# Kintex7_ssram.net
KiCad netlist of a schematic drawn in EAGLE
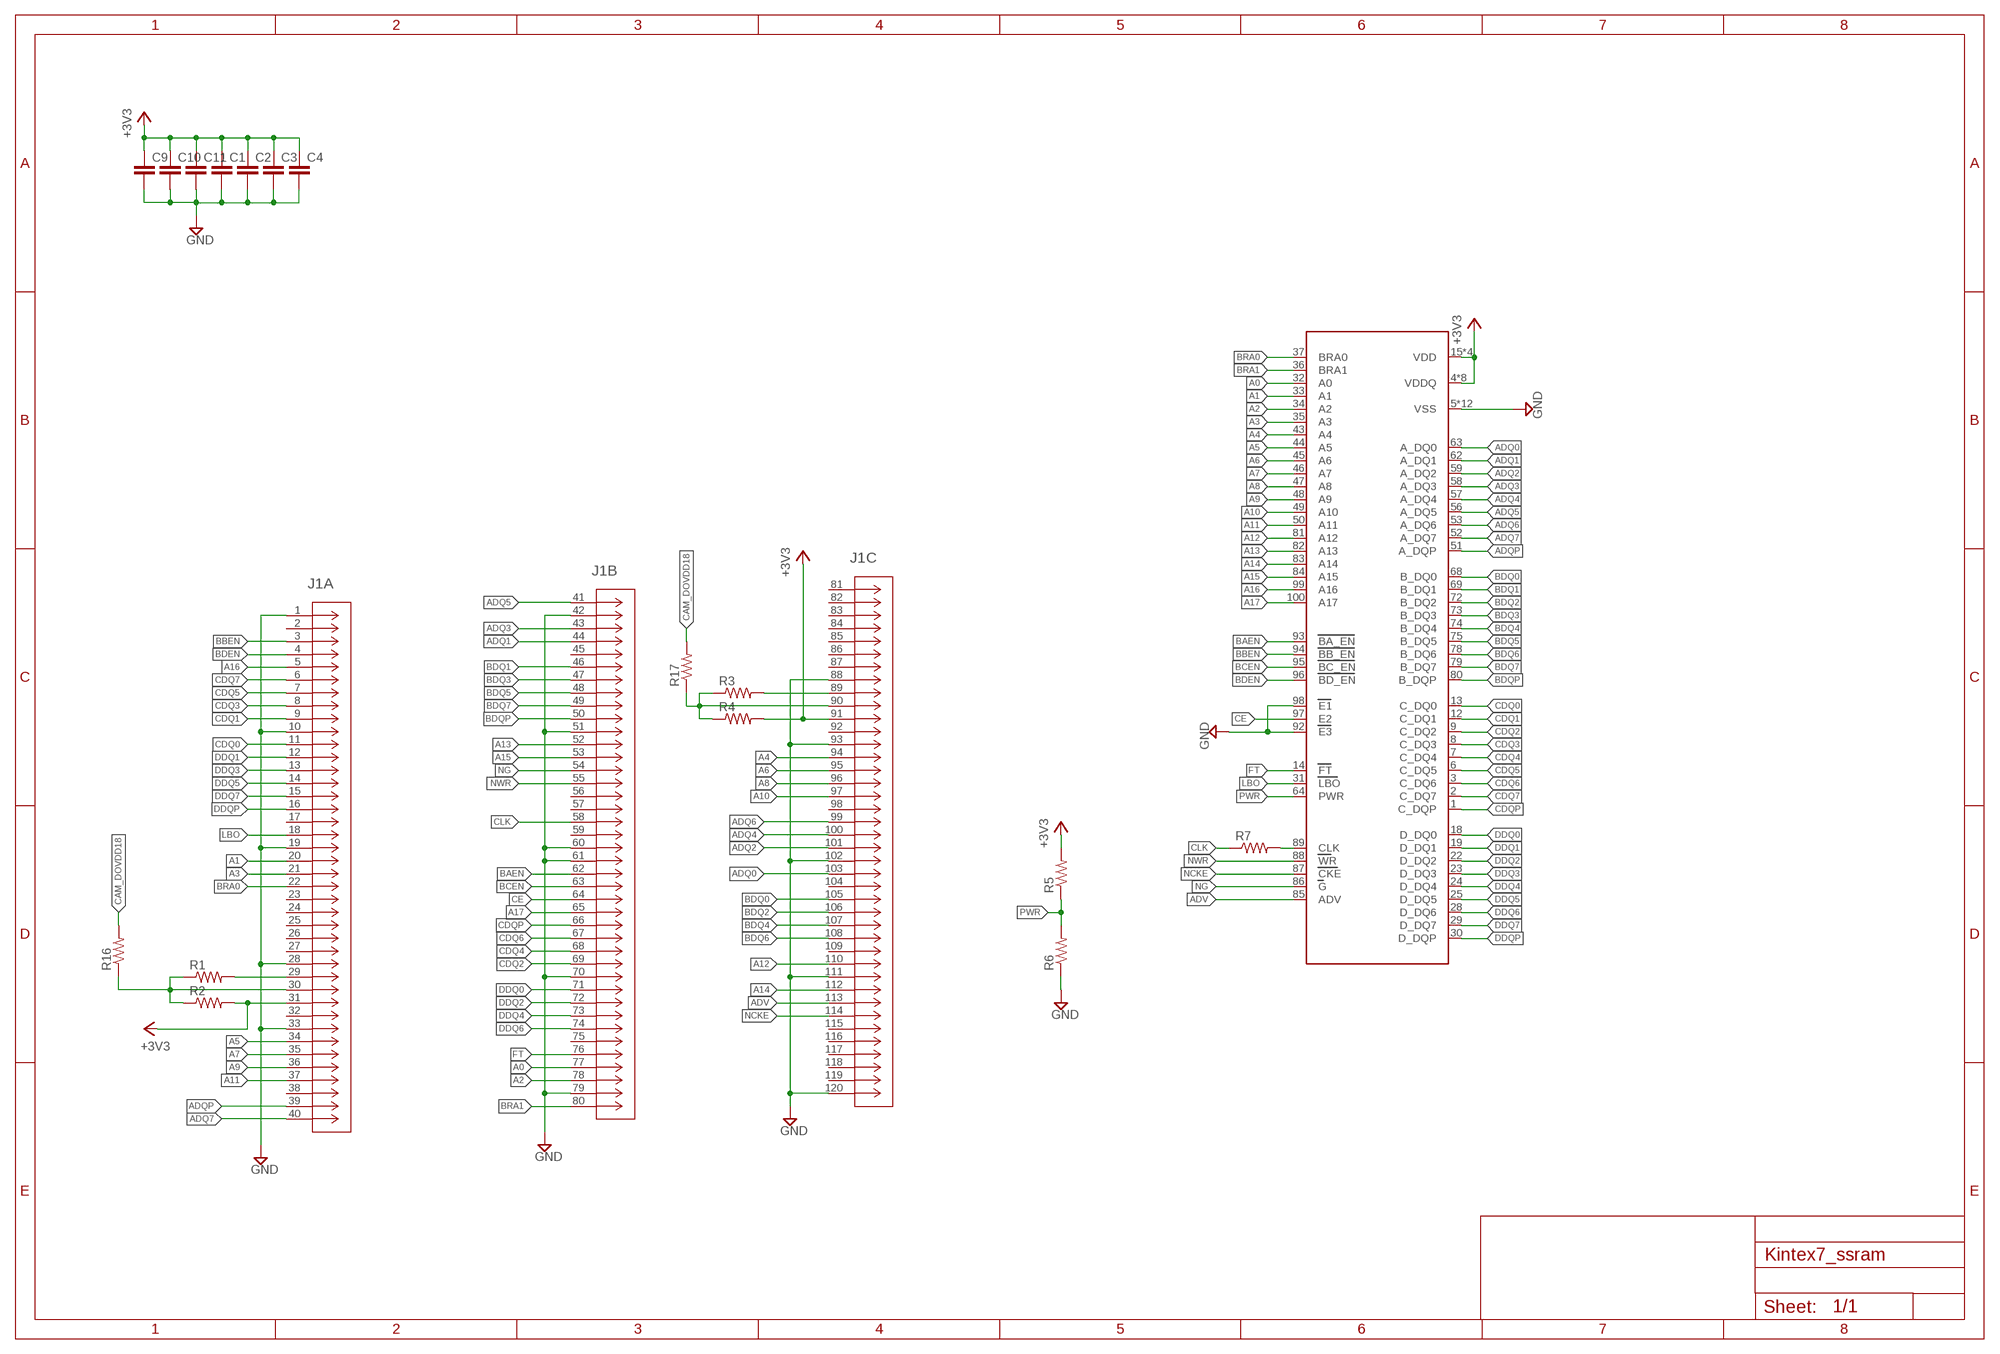
[diagram p0: schematic, sheet 1]

(export (version "E")
  (design (tool "Eeschema 10.0.6"))
  (components
    (comp (ref "C1")
      (value "C-EUC0603")
      (footprint "eagle-import:C0603")
      (libsource (lib "eagle-import") (part "C-EUC0603"))
    )
    (comp (ref "C2")
      (value "C-EUC0603")
      (footprint "eagle-import:C0603")
      (libsource (lib "eagle-import") (part "C-EUC0603"))
    )
    (comp (ref "C3")
      (value "C-EUC0603")
      (footprint "eagle-import:C0603")
      (libsource (lib "eagle-import") (part "C-EUC0603"))
    )
    (comp (ref "C4")
      (value "C-EUC0603")
      (footprint "eagle-import:C0603")
      (libsource (lib "eagle-import") (part "C-EUC0603"))
    )
    (comp (ref "C9")
      (value "C-EUC0603")
      (footprint "eagle-import:C0603")
      (libsource (lib "eagle-import") (part "C-EUC0603"))
    )
    (comp (ref "C10")
      (value "C-EUC0603")
      (footprint "eagle-import:C0603")
      (libsource (lib "eagle-import") (part "C-EUC0603"))
    )
    (comp (ref "C11")
      (value "C-EUC0603")
      (footprint "eagle-import:C0603")
      (libsource (lib "eagle-import") (part "C-EUC0603"))
    )
    (comp (ref "J1")
      (value "5177985-5")
      (footprint "eagle-import:CONN_5177985-5")
      (libsource (lib "eagle-import") (part "5177985-5"))
    )
    (comp (ref "R1")
      (value "R-US_R0805")
      (footprint "eagle-import:R0805")
      (libsource (lib "eagle-import") (part "R-US_R0805"))
    )
    (comp (ref "R2")
      (value "R-US_R0805")
      (footprint "eagle-import:R0805")
      (libsource (lib "eagle-import") (part "R-US_R0805"))
    )
    (comp (ref "R3")
      (value "R-US_R0805")
      (footprint "eagle-import:R0805")
      (libsource (lib "eagle-import") (part "R-US_R0805"))
    )
    (comp (ref "R4")
      (value "R-US_R0805")
      (footprint "eagle-import:R0805")
      (libsource (lib "eagle-import") (part "R-US_R0805"))
    )
    (comp (ref "R5")
      (value "R-US_R0603")
      (footprint "eagle-import:R0603")
      (libsource (lib "eagle-import") (part "R-US_R0603"))
    )
    (comp (ref "R6")
      (value "R-US_R0603")
      (footprint "eagle-import:R0603")
      (libsource (lib "eagle-import") (part "R-US_R0603"))
    )
    (comp (ref "R7")
      (value "R-US_R0603")
      (footprint "eagle-import:R0603")
      (libsource (lib "eagle-import") (part "R-US_R0603"))
    )
    (comp (ref "R16")
      (value "R-US_R0805")
      (footprint "eagle-import:R0805")
      (libsource (lib "eagle-import") (part "R-US_R0805"))
    )
    (comp (ref "R17")
      (value "R-US_R0805")
      (footprint "eagle-import:R0805")
      (libsource (lib "eagle-import") (part "R-US_R0805"))
    )
    (comp (ref "RAM")
      (value "GS8320Z36GTSMT")
      (footprint "eagle-import:TQFP100-R")
      (libsource (lib "eagle-import") (part "GS8320Z36GTSMT"))
    )
  )
  (nets
    (net (code "1") (name "+3V3") (class "Default")
      (node (ref "C1") (pin "1") (pinfunction "1_1") (pintype "passive"))
      (node (ref "C10") (pin "1") (pinfunction "1_1") (pintype "passive"))
      (node (ref "C11") (pin "1") (pinfunction "1_1") (pintype "passive"))
      (node (ref "C2") (pin "1") (pinfunction "1_1") (pintype "passive"))
      (node (ref "C3") (pin "1") (pinfunction "1_1") (pintype "passive"))
      (node (ref "C4") (pin "1") (pinfunction "1_1") (pintype "passive"))
      (node (ref "C9") (pin "1") (pinfunction "1_1") (pintype "passive"))
      (node (ref "J1") (pin "31") (pinfunction "31_31") (pintype "passive"))
      (node (ref "J1") (pin "91") (pinfunction "91_91") (pintype "passive"))
      (node (ref "R2") (pin "2") (pinfunction "2_2") (pintype "passive"))
      (node (ref "R4") (pin "2") (pinfunction "2_2") (pintype "passive"))
      (node (ref "R5") (pin "2") (pinfunction "2_2") (pintype "passive"))
      (node (ref "RAM") (pin "11") (pinfunction "VDDQ_11") (pintype "power_in"))
      (node (ref "RAM") (pin "15") (pinfunction "VDD_15") (pintype "power_in"))
      (node (ref "RAM") (pin "20") (pinfunction "VDDQ_20") (pintype "power_in"))
      (node (ref "RAM") (pin "27") (pinfunction "VDDQ_27") (pintype "power_in"))
      (node (ref "RAM") (pin "4") (pinfunction "VDDQ_4") (pintype "power_in"))
      (node (ref "RAM") (pin "41") (pinfunction "VDD_41") (pintype "power_in"))
      (node (ref "RAM") (pin "54") (pinfunction "VDDQ_54") (pintype "power_in"))
      (node (ref "RAM") (pin "61") (pinfunction "VDDQ_61") (pintype "power_in"))
      (node (ref "RAM") (pin "65") (pinfunction "VDD_65") (pintype "power_in"))
      (node (ref "RAM") (pin "70") (pinfunction "VDDQ_70") (pintype "power_in"))
      (node (ref "RAM") (pin "77") (pinfunction "VDDQ_77") (pintype "power_in"))
      (node (ref "RAM") (pin "91") (pinfunction "VDD_91") (pintype "power_in"))
    )
    (net (code "2") (name "A0") (class "Default")
      (node (ref "J1") (pin "77") (pinfunction "77_77") (pintype "passive"))
      (node (ref "RAM") (pin "32") (pinfunction "A0_32") (pintype "input"))
    )
    (net (code "3") (name "A1") (class "Default")
      (node (ref "J1") (pin "20") (pinfunction "20_20") (pintype "passive"))
      (node (ref "RAM") (pin "33") (pinfunction "A1_33") (pintype "input"))
    )
    (net (code "4") (name "A2") (class "Default")
      (node (ref "J1") (pin "78") (pinfunction "78_78") (pintype "passive"))
      (node (ref "RAM") (pin "34") (pinfunction "A2_34") (pintype "input"))
    )
    (net (code "5") (name "A3") (class "Default")
      (node (ref "J1") (pin "21") (pinfunction "21_21") (pintype "passive"))
      (node (ref "RAM") (pin "35") (pinfunction "A3_35") (pintype "input"))
    )
    (net (code "6") (name "A4") (class "Default")
      (node (ref "J1") (pin "94") (pinfunction "94_94") (pintype "passive"))
      (node (ref "RAM") (pin "43") (pinfunction "A4_43") (pintype "input"))
    )
    (net (code "7") (name "A5") (class "Default")
      (node (ref "J1") (pin "34") (pinfunction "34_34") (pintype "passive"))
      (node (ref "RAM") (pin "44") (pinfunction "A5_44") (pintype "input"))
    )
    (net (code "8") (name "A6") (class "Default")
      (node (ref "J1") (pin "95") (pinfunction "95_95") (pintype "passive"))
      (node (ref "RAM") (pin "45") (pinfunction "A6_45") (pintype "input"))
    )
    (net (code "9") (name "A7") (class "Default")
      (node (ref "J1") (pin "35") (pinfunction "35_35") (pintype "passive"))
      (node (ref "RAM") (pin "46") (pinfunction "A7_46") (pintype "input"))
    )
    (net (code "10") (name "A8") (class "Default")
      (node (ref "J1") (pin "96") (pinfunction "96_96") (pintype "passive"))
      (node (ref "RAM") (pin "47") (pinfunction "A8_47") (pintype "input"))
    )
    (net (code "11") (name "A9") (class "Default")
      (node (ref "J1") (pin "36") (pinfunction "36_36") (pintype "passive"))
      (node (ref "RAM") (pin "48") (pinfunction "A9_48") (pintype "input"))
    )
    (net (code "12") (name "A10") (class "Default")
      (node (ref "J1") (pin "97") (pinfunction "97_97") (pintype "passive"))
      (node (ref "RAM") (pin "49") (pinfunction "A10_49") (pintype "input"))
    )
    (net (code "13") (name "A11") (class "Default")
      (node (ref "J1") (pin "37") (pinfunction "37_37") (pintype "passive"))
      (node (ref "RAM") (pin "50") (pinfunction "A11_50") (pintype "input"))
    )
    (net (code "14") (name "A12") (class "Default")
      (node (ref "J1") (pin "110") (pinfunction "110_110") (pintype "passive"))
      (node (ref "RAM") (pin "81") (pinfunction "A12_81") (pintype "input"))
    )
    (net (code "15") (name "A13") (class "Default")
      (node (ref "J1") (pin "52") (pinfunction "52_52") (pintype "passive"))
      (node (ref "RAM") (pin "82") (pinfunction "A13_82") (pintype "input"))
    )
    (net (code "16") (name "A14") (class "Default")
      (node (ref "J1") (pin "112") (pinfunction "112_112") (pintype "passive"))
      (node (ref "RAM") (pin "83") (pinfunction "A14_83") (pintype "input"))
    )
    (net (code "17") (name "A15") (class "Default")
      (node (ref "J1") (pin "53") (pinfunction "53_53") (pintype "passive"))
      (node (ref "RAM") (pin "84") (pinfunction "A15_84") (pintype "input"))
    )
    (net (code "18") (name "A16") (class "Default")
      (node (ref "J1") (pin "5") (pinfunction "5_5") (pintype "passive"))
      (node (ref "RAM") (pin "99") (pinfunction "A16_99") (pintype "input"))
    )
    (net (code "19") (name "A17") (class "Default")
      (node (ref "J1") (pin "65") (pinfunction "65_65") (pintype "passive"))
      (node (ref "RAM") (pin "100") (pinfunction "A17_100") (pintype "input"))
    )
    (net (code "20") (name "ADQ0") (class "Default")
      (node (ref "J1") (pin "103") (pinfunction "103_103") (pintype "passive"))
      (node (ref "RAM") (pin "63") (pinfunction "A_DQ0_63") (pintype "bidirectional"))
    )
    (net (code "21") (name "ADQ1") (class "Default")
      (node (ref "J1") (pin "44") (pinfunction "44_44") (pintype "passive"))
      (node (ref "RAM") (pin "62") (pinfunction "A_DQ1_62") (pintype "bidirectional"))
    )
    (net (code "22") (name "ADQ2") (class "Default")
      (node (ref "J1") (pin "101") (pinfunction "101_101") (pintype "passive"))
      (node (ref "RAM") (pin "59") (pinfunction "A_DQ2_59") (pintype "bidirectional"))
    )
    (net (code "23") (name "ADQ3") (class "Default")
      (node (ref "J1") (pin "43") (pinfunction "43_43") (pintype "passive"))
      (node (ref "RAM") (pin "58") (pinfunction "A_DQ3_58") (pintype "bidirectional"))
    )
    (net (code "24") (name "ADQ4") (class "Default")
      (node (ref "J1") (pin "100") (pinfunction "100_100") (pintype "passive"))
      (node (ref "RAM") (pin "57") (pinfunction "A_DQ4_57") (pintype "bidirectional"))
    )
    (net (code "25") (name "ADQ5") (class "Default")
      (node (ref "J1") (pin "41") (pinfunction "41_41") (pintype "passive"))
      (node (ref "RAM") (pin "56") (pinfunction "A_DQ5_56") (pintype "bidirectional"))
    )
    (net (code "26") (name "ADQ6") (class "Default")
      (node (ref "J1") (pin "99") (pinfunction "99_99") (pintype "passive"))
      (node (ref "RAM") (pin "53") (pinfunction "A_DQ6_53") (pintype "bidirectional"))
    )
    (net (code "27") (name "ADQ7") (class "Default")
      (node (ref "J1") (pin "40") (pinfunction "40_40") (pintype "passive"))
      (node (ref "RAM") (pin "52") (pinfunction "A_DQ7_52") (pintype "bidirectional"))
    )
    (net (code "28") (name "ADQP") (class "Default")
      (node (ref "J1") (pin "39") (pinfunction "39_39") (pintype "passive"))
      (node (ref "RAM") (pin "51") (pinfunction "A_DQP_51") (pintype "bidirectional"))
    )
    (net (code "29") (name "ADV") (class "Default")
      (node (ref "J1") (pin "113") (pinfunction "113_113") (pintype "passive"))
      (node (ref "RAM") (pin "85") (pinfunction "ADV_85") (pintype "input"))
    )
    (net (code "30") (name "BAEN") (class "Default")
      (node (ref "J1") (pin "62") (pinfunction "62_62") (pintype "passive"))
      (node (ref "RAM") (pin "93") (pinfunction "BA_EN_93") (pintype "input"))
    )
    (net (code "31") (name "BBEN") (class "Default")
      (node (ref "J1") (pin "3") (pinfunction "3_3") (pintype "passive"))
      (node (ref "RAM") (pin "94") (pinfunction "BB_EN_94") (pintype "input"))
    )
    (net (code "32") (name "BCEN") (class "Default")
      (node (ref "J1") (pin "63") (pinfunction "63_63") (pintype "passive"))
      (node (ref "RAM") (pin "95") (pinfunction "BC_EN_95") (pintype "input"))
    )
    (net (code "33") (name "BDEN") (class "Default")
      (node (ref "J1") (pin "4") (pinfunction "4_4") (pintype "passive"))
      (node (ref "RAM") (pin "96") (pinfunction "BD_EN_96") (pintype "input"))
    )
    (net (code "34") (name "BDQ0") (class "Default")
      (node (ref "J1") (pin "105") (pinfunction "105_105") (pintype "passive"))
      (node (ref "RAM") (pin "68") (pinfunction "B_DQ0_68") (pintype "bidirectional"))
    )
    (net (code "35") (name "BDQ1") (class "Default")
      (node (ref "J1") (pin "46") (pinfunction "46_46") (pintype "passive"))
      (node (ref "RAM") (pin "69") (pinfunction "B_DQ1_69") (pintype "bidirectional"))
    )
    (net (code "36") (name "BDQ2") (class "Default")
      (node (ref "J1") (pin "106") (pinfunction "106_106") (pintype "passive"))
      (node (ref "RAM") (pin "72") (pinfunction "B_DQ2_72") (pintype "bidirectional"))
    )
    (net (code "37") (name "BDQ3") (class "Default")
      (node (ref "J1") (pin "47") (pinfunction "47_47") (pintype "passive"))
      (node (ref "RAM") (pin "73") (pinfunction "B_DQ3_73") (pintype "bidirectional"))
    )
    (net (code "38") (name "BDQ4") (class "Default")
      (node (ref "J1") (pin "107") (pinfunction "107_107") (pintype "passive"))
      (node (ref "RAM") (pin "74") (pinfunction "B_DQ4_74") (pintype "bidirectional"))
    )
    (net (code "39") (name "BDQ5") (class "Default")
      (node (ref "J1") (pin "48") (pinfunction "48_48") (pintype "passive"))
      (node (ref "RAM") (pin "75") (pinfunction "B_DQ5_75") (pintype "bidirectional"))
    )
    (net (code "40") (name "BDQ6") (class "Default")
      (node (ref "J1") (pin "108") (pinfunction "108_108") (pintype "passive"))
      (node (ref "RAM") (pin "78") (pinfunction "B_DQ6_78") (pintype "bidirectional"))
    )
    (net (code "41") (name "BDQ7") (class "Default")
      (node (ref "J1") (pin "49") (pinfunction "49_49") (pintype "passive"))
      (node (ref "RAM") (pin "79") (pinfunction "B_DQ7_79") (pintype "bidirectional"))
    )
    (net (code "42") (name "BDQP") (class "Default")
      (node (ref "J1") (pin "50") (pinfunction "50_50") (pintype "passive"))
      (node (ref "RAM") (pin "80") (pinfunction "B_DQP_80") (pintype "bidirectional"))
    )
    (net (code "43") (name "BRA0") (class "Default")
      (node (ref "J1") (pin "22") (pinfunction "22_22") (pintype "passive"))
      (node (ref "RAM") (pin "37") (pinfunction "BRA0_37") (pintype "input"))
    )
    (net (code "44") (name "BRA1") (class "Default")
      (node (ref "J1") (pin "80") (pinfunction "80_80") (pintype "passive"))
      (node (ref "RAM") (pin "36") (pinfunction "BRA1_36") (pintype "input"))
    )
    (net (code "45") (name "CAM_DOVDD18") (class "Default")
      (node (ref "R16") (pin "2") (pinfunction "2_2") (pintype "passive"))
      (node (ref "R17") (pin "2") (pinfunction "2_2") (pintype "passive"))
    )
    (net (code "46") (name "CDQ0") (class "Default")
      (node (ref "J1") (pin "11") (pinfunction "11_11") (pintype "passive"))
      (node (ref "RAM") (pin "13") (pinfunction "C_DQ0_13") (pintype "bidirectional"))
    )
    (net (code "47") (name "CDQ1") (class "Default")
      (node (ref "J1") (pin "9") (pinfunction "9_9") (pintype "passive"))
      (node (ref "RAM") (pin "12") (pinfunction "C_DQ1_12") (pintype "bidirectional"))
    )
    (net (code "48") (name "CDQ2") (class "Default")
      (node (ref "J1") (pin "69") (pinfunction "69_69") (pintype "passive"))
      (node (ref "RAM") (pin "9") (pinfunction "C_DQ2_9") (pintype "bidirectional"))
    )
    (net (code "49") (name "CDQ3") (class "Default")
      (node (ref "J1") (pin "8") (pinfunction "8_8") (pintype "passive"))
      (node (ref "RAM") (pin "8") (pinfunction "C_DQ3_8") (pintype "bidirectional"))
    )
    (net (code "50") (name "CDQ4") (class "Default")
      (node (ref "J1") (pin "68") (pinfunction "68_68") (pintype "passive"))
      (node (ref "RAM") (pin "7") (pinfunction "C_DQ4_7") (pintype "bidirectional"))
    )
    (net (code "51") (name "CDQ5") (class "Default")
      (node (ref "J1") (pin "7") (pinfunction "7_7") (pintype "passive"))
      (node (ref "RAM") (pin "6") (pinfunction "C_DQ5_6") (pintype "bidirectional"))
    )
    (net (code "52") (name "CDQ6") (class "Default")
      (node (ref "J1") (pin "67") (pinfunction "67_67") (pintype "passive"))
      (node (ref "RAM") (pin "3") (pinfunction "C_DQ6_3") (pintype "bidirectional"))
    )
    (net (code "53") (name "CDQ7") (class "Default")
      (node (ref "J1") (pin "6") (pinfunction "6_6") (pintype "passive"))
      (node (ref "RAM") (pin "2") (pinfunction "C_DQ7_2") (pintype "bidirectional"))
    )
    (net (code "54") (name "CDQP") (class "Default")
      (node (ref "J1") (pin "66") (pinfunction "66_66") (pintype "passive"))
      (node (ref "RAM") (pin "1") (pinfunction "C_DQP_1") (pintype "bidirectional"))
    )
    (net (code "55") (name "CE") (class "Default")
      (node (ref "J1") (pin "64") (pinfunction "64_64") (pintype "passive"))
      (node (ref "RAM") (pin "97") (pinfunction "E2_97") (pintype "input"))
    )
    (net (code "56") (name "CLK") (class "Default")
      (node (ref "J1") (pin "58") (pinfunction "58_58") (pintype "passive"))
      (node (ref "R7") (pin "1") (pinfunction "1_1") (pintype "passive"))
    )
    (net (code "57") (name "DDQ0") (class "Default")
      (node (ref "J1") (pin "71") (pinfunction "71_71") (pintype "passive"))
      (node (ref "RAM") (pin "18") (pinfunction "D_DQ0_18") (pintype "bidirectional"))
    )
    (net (code "58") (name "DDQ1") (class "Default")
      (node (ref "J1") (pin "12") (pinfunction "12_12") (pintype "passive"))
      (node (ref "RAM") (pin "19") (pinfunction "D_DQ1_19") (pintype "bidirectional"))
    )
    (net (code "59") (name "DDQ2") (class "Default")
      (node (ref "J1") (pin "72") (pinfunction "72_72") (pintype "passive"))
      (node (ref "RAM") (pin "22") (pinfunction "D_DQ2_22") (pintype "bidirectional"))
    )
    (net (code "60") (name "DDQ3") (class "Default")
      (node (ref "J1") (pin "13") (pinfunction "13_13") (pintype "passive"))
      (node (ref "RAM") (pin "23") (pinfunction "D_DQ3_23") (pintype "bidirectional"))
    )
    (net (code "61") (name "DDQ4") (class "Default")
      (node (ref "J1") (pin "73") (pinfunction "73_73") (pintype "passive"))
      (node (ref "RAM") (pin "24") (pinfunction "D_DQ4_24") (pintype "bidirectional"))
    )
    (net (code "62") (name "DDQ5") (class "Default")
      (node (ref "J1") (pin "14") (pinfunction "14_14") (pintype "passive"))
      (node (ref "RAM") (pin "25") (pinfunction "D_DQ5_25") (pintype "bidirectional"))
    )
    (net (code "63") (name "DDQ6") (class "Default")
      (node (ref "J1") (pin "74") (pinfunction "74_74") (pintype "passive"))
      (node (ref "RAM") (pin "28") (pinfunction "D_DQ6_28") (pintype "bidirectional"))
    )
    (net (code "64") (name "DDQ7") (class "Default")
      (node (ref "J1") (pin "15") (pinfunction "15_15") (pintype "passive"))
      (node (ref "RAM") (pin "29") (pinfunction "D_DQ7_29") (pintype "bidirectional"))
    )
    (net (code "65") (name "DDQP") (class "Default")
      (node (ref "J1") (pin "16") (pinfunction "16_16") (pintype "passive"))
      (node (ref "RAM") (pin "30") (pinfunction "D_DQP_30") (pintype "bidirectional"))
    )
    (net (code "66") (name "FT") (class "Default")
      (node (ref "J1") (pin "76") (pinfunction "76_76") (pintype "passive"))
      (node (ref "RAM") (pin "14") (pinfunction "FT_14") (pintype "input"))
    )
    (net (code "67") (name "GND") (class "Default")
      (node (ref "C1") (pin "2") (pinfunction "2_2") (pintype "passive"))
      (node (ref "C10") (pin "2") (pinfunction "2_2") (pintype "passive"))
      (node (ref "C11") (pin "2") (pinfunction "2_2") (pintype "passive"))
      (node (ref "C2") (pin "2") (pinfunction "2_2") (pintype "passive"))
      (node (ref "C3") (pin "2") (pinfunction "2_2") (pintype "passive"))
      (node (ref "C4") (pin "2") (pinfunction "2_2") (pintype "passive"))
      (node (ref "C9") (pin "2") (pinfunction "2_2") (pintype "passive"))
      (node (ref "J1") (pin "1") (pinfunction "1_1") (pintype "passive"))
      (node (ref "J1") (pin "10") (pinfunction "10_10") (pintype "passive"))
      (node (ref "J1") (pin "102") (pinfunction "102_102") (pintype "passive"))
      (node (ref "J1") (pin "111") (pinfunction "111_111") (pintype "passive"))
      (node (ref "J1") (pin "120") (pinfunction "120_120") (pintype "passive"))
      (node (ref "J1") (pin "19") (pinfunction "19_19") (pintype "passive"))
      (node (ref "J1") (pin "28") (pinfunction "28_28") (pintype "passive"))
      (node (ref "J1") (pin "33") (pinfunction "33_33") (pintype "passive"))
      (node (ref "J1") (pin "42") (pinfunction "42_42") (pintype "passive"))
      (node (ref "J1") (pin "51") (pinfunction "51_51") (pintype "passive"))
      (node (ref "J1") (pin "60") (pinfunction "60_60") (pintype "passive"))
      (node (ref "J1") (pin "61") (pinfunction "61_61") (pintype "passive"))
      (node (ref "J1") (pin "70") (pinfunction "70_70") (pintype "passive"))
      (node (ref "J1") (pin "79") (pinfunction "79_79") (pintype "passive"))
      (node (ref "J1") (pin "88") (pinfunction "88_88") (pintype "passive"))
      (node (ref "J1") (pin "93") (pinfunction "93_93") (pintype "passive"))
      (node (ref "R6") (pin "1") (pinfunction "1_1") (pintype "passive"))
      (node (ref "RAM") (pin "10") (pinfunction "VSS_10") (pintype "power_in"))
      (node (ref "RAM") (pin "17") (pinfunction "VSS_17") (pintype "power_in"))
      (node (ref "RAM") (pin "21") (pinfunction "VSS_21") (pintype "power_in"))
      (node (ref "RAM") (pin "26") (pinfunction "VSS_26") (pintype "power_in"))
      (node (ref "RAM") (pin "40") (pinfunction "VSS_40") (pintype "power_in"))
      (node (ref "RAM") (pin "5") (pinfunction "VSS_5") (pintype "power_in"))
      (node (ref "RAM") (pin "55") (pinfunction "VSS_55") (pintype "power_in"))
      (node (ref "RAM") (pin "60") (pinfunction "VSS_60") (pintype "power_in"))
      (node (ref "RAM") (pin "67") (pinfunction "VSS_67") (pintype "power_in"))
      (node (ref "RAM") (pin "71") (pinfunction "VSS_71") (pintype "power_in"))
      (node (ref "RAM") (pin "76") (pinfunction "VSS_76") (pintype "power_in"))
      (node (ref "RAM") (pin "90") (pinfunction "VSS_90") (pintype "power_in"))
      (node (ref "RAM") (pin "92") (pinfunction "E3_92") (pintype "input"))
      (node (ref "RAM") (pin "98") (pinfunction "E1_98") (pintype "input"))
    )
    (net (code "68") (name "LBO") (class "Default")
      (node (ref "J1") (pin "18") (pinfunction "18_18") (pintype "passive"))
      (node (ref "RAM") (pin "31") (pinfunction "LBO_31") (pintype "input"))
    )
    (net (code "69") (name "NCKE") (class "Default")
      (node (ref "J1") (pin "114") (pinfunction "114_114") (pintype "passive"))
      (node (ref "RAM") (pin "87") (pinfunction "CKE_87") (pintype "input"))
    )
    (net (code "70") (name "NG") (class "Default")
      (node (ref "J1") (pin "54") (pinfunction "54_54") (pintype "passive"))
      (node (ref "RAM") (pin "86") (pinfunction "G_86") (pintype "input"))
    )
    (net (code "71") (name "NWR") (class "Default")
      (node (ref "J1") (pin "55") (pinfunction "55_55") (pintype "passive"))
      (node (ref "RAM") (pin "88") (pinfunction "WR_88") (pintype "input"))
    )
    (net (code "72") (name "Net-(J1-Pad29)") (class "Default")
      (node (ref "J1") (pin "29") (pinfunction "29_29") (pintype "passive"))
      (node (ref "R1") (pin "2") (pinfunction "2_2") (pintype "passive"))
    )
    (net (code "73") (name "Net-(J1-Pad30)") (class "Default")
      (node (ref "J1") (pin "30") (pinfunction "30_30") (pintype "passive"))
      (node (ref "R1") (pin "1") (pinfunction "1_1") (pintype "passive"))
      (node (ref "R16") (pin "1") (pinfunction "1_1") (pintype "passive"))
      (node (ref "R2") (pin "1") (pinfunction "1_1") (pintype "passive"))
    )
    (net (code "74") (name "Net-(J1-Pad89)") (class "Default")
      (node (ref "J1") (pin "89") (pinfunction "89_89") (pintype "passive"))
      (node (ref "R3") (pin "2") (pinfunction "2_2") (pintype "passive"))
    )
    (net (code "75") (name "Net-(J1-Pad90)") (class "Default")
      (node (ref "J1") (pin "90") (pinfunction "90_90") (pintype "passive"))
      (node (ref "R17") (pin "1") (pinfunction "1_1") (pintype "passive"))
      (node (ref "R3") (pin "1") (pinfunction "1_1") (pintype "passive"))
      (node (ref "R4") (pin "1") (pinfunction "1_1") (pintype "passive"))
    )
    (net (code "76") (name "Net-(RAM-CLK)") (class "Default")
      (node (ref "R7") (pin "2") (pinfunction "2_2") (pintype "passive"))
      (node (ref "RAM") (pin "89") (pinfunction "CLK_89") (pintype "input"))
    )
    (net (code "77") (name "PWR") (class "Default")
      (node (ref "R5") (pin "1") (pinfunction "1_1") (pintype "passive"))
      (node (ref "R6") (pin "2") (pinfunction "2_2") (pintype "passive"))
      (node (ref "RAM") (pin "64") (pinfunction "PWR_64") (pintype "input"))
    )
    (net (code "78") (name "unconnected-(J1-Pad2)") (class "Default")
      (node (ref "J1") (pin "2") (pinfunction "2_2") (pintype "passive"))
    )
    (net (code "79") (name "unconnected-(J1-Pad17)") (class "Default")
      (node (ref "J1") (pin "17") (pinfunction "17_17") (pintype "passive"))
    )
    (net (code "80") (name "unconnected-(J1-Pad23)") (class "Default")
      (node (ref "J1") (pin "23") (pinfunction "23_23") (pintype "passive"))
    )
    (net (code "81") (name "unconnected-(J1-Pad24)") (class "Default")
      (node (ref "J1") (pin "24") (pinfunction "24_24") (pintype "passive"))
    )
    (net (code "82") (name "unconnected-(J1-Pad25)") (class "Default")
      (node (ref "J1") (pin "25") (pinfunction "25_25") (pintype "passive"))
    )
    (net (code "83") (name "unconnected-(J1-Pad26)") (class "Default")
      (node (ref "J1") (pin "26") (pinfunction "26_26") (pintype "passive"))
    )
    (net (code "84") (name "unconnected-(J1-Pad27)") (class "Default")
      (node (ref "J1") (pin "27") (pinfunction "27_27") (pintype "passive"))
    )
    (net (code "85") (name "unconnected-(J1-Pad32)") (class "Default")
      (node (ref "J1") (pin "32") (pinfunction "32_32") (pintype "passive"))
    )
    (net (code "86") (name "unconnected-(J1-Pad38)") (class "Default")
      (node (ref "J1") (pin "38") (pinfunction "38_38") (pintype "passive"))
    )
    (net (code "87") (name "unconnected-(J1-Pad45)") (class "Default")
      (node (ref "J1") (pin "45") (pinfunction "45_45") (pintype "passive"))
    )
    (net (code "88") (name "unconnected-(J1-Pad56)") (class "Default")
      (node (ref "J1") (pin "56") (pinfunction "56_56") (pintype "passive"))
    )
    (net (code "89") (name "unconnected-(J1-Pad57)") (class "Default")
      (node (ref "J1") (pin "57") (pinfunction "57_57") (pintype "passive"))
    )
    (net (code "90") (name "unconnected-(J1-Pad59)") (class "Default")
      (node (ref "J1") (pin "59") (pinfunction "59_59") (pintype "passive"))
    )
    (net (code "91") (name "unconnected-(J1-Pad75)") (class "Default")
      (node (ref "J1") (pin "75") (pinfunction "75_75") (pintype "passive"))
    )
    (net (code "92") (name "unconnected-(J1-Pad81)") (class "Default")
      (node (ref "J1") (pin "81") (pinfunction "81_81") (pintype "passive"))
    )
    (net (code "93") (name "unconnected-(J1-Pad82)") (class "Default")
      (node (ref "J1") (pin "82") (pinfunction "82_82") (pintype "passive"))
    )
    (net (code "94") (name "unconnected-(J1-Pad83)") (class "Default")
      (node (ref "J1") (pin "83") (pinfunction "83_83") (pintype "passive"))
    )
    (net (code "95") (name "unconnected-(J1-Pad84)") (class "Default")
      (node (ref "J1") (pin "84") (pinfunction "84_84") (pintype "passive"))
    )
    (net (code "96") (name "unconnected-(J1-Pad85)") (class "Default")
      (node (ref "J1") (pin "85") (pinfunction "85_85") (pintype "passive"))
    )
    (net (code "97") (name "unconnected-(J1-Pad86)") (class "Default")
      (node (ref "J1") (pin "86") (pinfunction "86_86") (pintype "passive"))
    )
    (net (code "98") (name "unconnected-(J1-Pad87)") (class "Default")
      (node (ref "J1") (pin "87") (pinfunction "87_87") (pintype "passive"))
    )
    (net (code "99") (name "unconnected-(J1-Pad92)") (class "Default")
      (node (ref "J1") (pin "92") (pinfunction "92_92") (pintype "passive"))
    )
    (net (code "100") (name "unconnected-(J1-Pad98)") (class "Default")
      (node (ref "J1") (pin "98") (pinfunction "98_98") (pintype "passive"))
    )
    (net (code "101") (name "unconnected-(J1-Pad104)") (class "Default")
      (node (ref "J1") (pin "104") (pinfunction "104_104") (pintype "passive"))
    )
    (net (code "102") (name "unconnected-(J1-Pad109)") (class "Default")
      (node (ref "J1") (pin "109") (pinfunction "109_109") (pintype "passive"))
    )
    (net (code "103") (name "unconnected-(J1-Pad115)") (class "Default")
      (node (ref "J1") (pin "115") (pinfunction "115_115") (pintype "passive"))
    )
    (net (code "104") (name "unconnected-(J1-Pad116)") (class "Default")
      (node (ref "J1") (pin "116") (pinfunction "116_116") (pintype "passive"))
    )
    (net (code "105") (name "unconnected-(J1-Pad117)") (class "Default")
      (node (ref "J1") (pin "117") (pinfunction "117_117") (pintype "passive"))
    )
    (net (code "106") (name "unconnected-(J1-Pad118)") (class "Default")
      (node (ref "J1") (pin "118") (pinfunction "118_118") (pintype "passive"))
    )
    (net (code "107") (name "unconnected-(J1-Pad119)") (class "Default")
      (node (ref "J1") (pin "119") (pinfunction "119_119") (pintype "passive"))
    )
  )
)
